# CC_AMP.net
KiCad netlist of a schematic drawn in Altium Designer
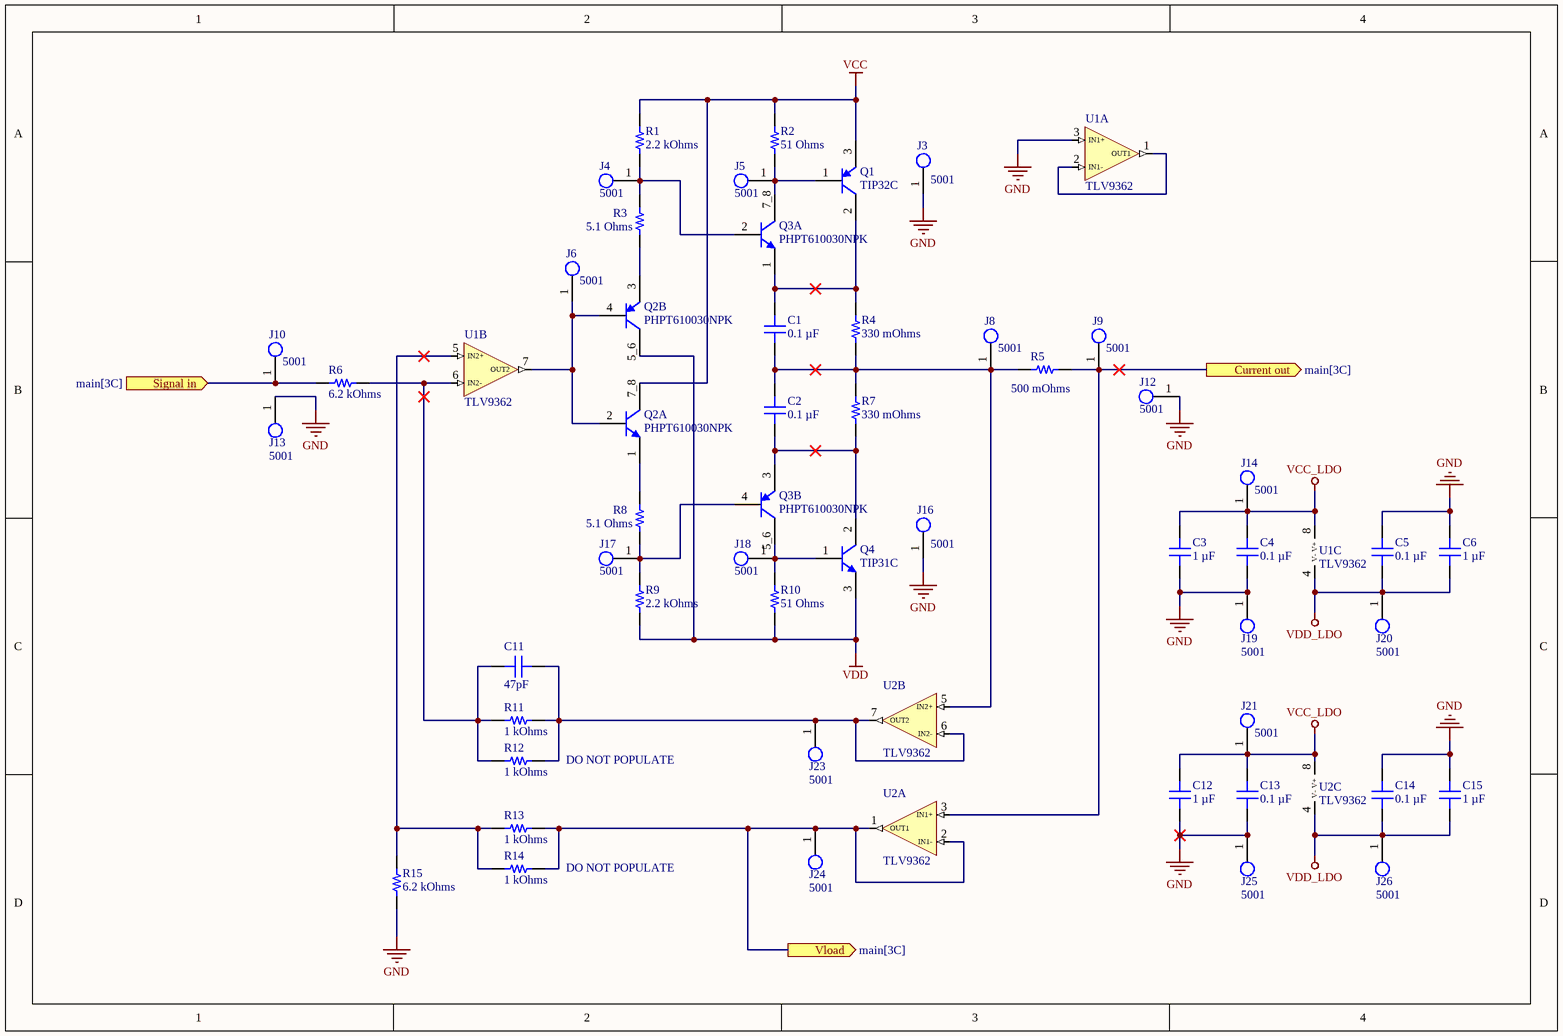
[diagram p0: CC_AMP.SchDoc]

(export (version "E")
  (design (tool "Eeschema 10.0.6"))
  (components
    (comp (ref "C1")
      (value "0.1 µF")
      (footprint "CAP 1206_3216 - 0.8MM")
      (description "CAP CER 0.1UF 50V X7R 1206")
      (fields
        (field (name "PART NUMBER") "885012208087")
        (field (name "CAPACITANCE") "0.1 µF")
        (field (name "MANUFACTURER") "Würth Elektronik")
      )
      (libsource (lib "Celestial Altium Library - altium_library") (part "Capacitor"))
    )
    (comp (ref "C2")
      (value "0.1 µF")
      (footprint "CAP 1206_3216 - 0.8MM")
      (description "CAP CER 0.1UF 50V X7R 1206")
      (fields
        (field (name "PART NUMBER") "885012208087")
        (field (name "CAPACITANCE") "0.1 µF")
        (field (name "MANUFACTURER") "Würth Elektronik")
      )
      (libsource (lib "Celestial Altium Library - altium_library") (part "Capacitor"))
    )
    (comp (ref "C3")
      (value "1 µF")
      (footprint "CAP 1206_3216 - 0.8MM")
      (description "CAP CER 1UF 50V X7R 1206")
      (fields
        (field (name "PART NUMBER") "885012208093")
        (field (name "CAPACITANCE") "1 µF")
        (field (name "MANUFACTURER") "Würth Elektronik")
      )
      (libsource (lib "Celestial Altium Library - altium_library") (part "Capacitor"))
    )
    (comp (ref "C4")
      (value "0.1 µF")
      (footprint "CAP 1206_3216 - 0.8MM")
      (description "CAP CER 0.1UF 50V X7R 1206")
      (fields
        (field (name "PART NUMBER") "885012208087")
        (field (name "CAPACITANCE") "0.1 µF")
        (field (name "MANUFACTURER") "Würth Elektronik")
      )
      (libsource (lib "Celestial Altium Library - altium_library") (part "Capacitor"))
    )
    (comp (ref "C5")
      (value "0.1 µF")
      (footprint "CAP 1206_3216 - 0.8MM")
      (description "CAP CER 0.1UF 50V X7R 1206")
      (fields
        (field (name "PART NUMBER") "885012208087")
        (field (name "CAPACITANCE") "0.1 µF")
        (field (name "MANUFACTURER") "Würth Elektronik")
      )
      (libsource (lib "Celestial Altium Library - altium_library") (part "Capacitor"))
    )
    (comp (ref "C6")
      (value "1 µF")
      (footprint "CAP 1206_3216 - 0.8MM")
      (description "CAP CER 1UF 50V X7R 1206")
      (fields
        (field (name "PART NUMBER") "885012208093")
        (field (name "CAPACITANCE") "1 µF")
        (field (name "MANUFACTURER") "Würth Elektronik")
      )
      (libsource (lib "Celestial Altium Library - altium_library") (part "Capacitor"))
    )
    (comp (ref "C11")
      (value "47pF")
      (footprint "CAP 1206_3216 - 1.8MM")
      (description "CAP CER 47PF 1KV C0G/NP0 1206")
      (fields
        (field (name "PART NUMBER") "1206AA470KAT1A")
        (field (name "CAPACITANCE") "47pF")
        (field (name "MANUFACTURER") "AVX Corporation")
      )
      (libsource (lib "Celestial Altium Library - altium_library") (part "Capacitor"))
    )
    (comp (ref "C12")
      (value "1 µF")
      (footprint "CAP 1206_3216 - 0.8MM")
      (description "CAP CER 1UF 50V X7R 1206")
      (fields
        (field (name "PART NUMBER") "885012208093")
        (field (name "CAPACITANCE") "1 µF")
        (field (name "MANUFACTURER") "Würth Elektronik")
      )
      (libsource (lib "Celestial Altium Library - altium_library") (part "Capacitor"))
    )
    (comp (ref "C13")
      (value "0.1 µF")
      (footprint "CAP 1206_3216 - 0.8MM")
      (description "CAP CER 0.1UF 50V X7R 1206")
      (fields
        (field (name "PART NUMBER") "885012208087")
        (field (name "CAPACITANCE") "0.1 µF")
        (field (name "MANUFACTURER") "Würth Elektronik")
      )
      (libsource (lib "Celestial Altium Library - altium_library") (part "Capacitor"))
    )
    (comp (ref "C14")
      (value "0.1 µF")
      (footprint "CAP 1206_3216 - 0.8MM")
      (description "CAP CER 0.1UF 50V X7R 1206")
      (fields
        (field (name "PART NUMBER") "885012208087")
        (field (name "CAPACITANCE") "0.1 µF")
        (field (name "MANUFACTURER") "Würth Elektronik")
      )
      (libsource (lib "Celestial Altium Library - altium_library") (part "Capacitor"))
    )
    (comp (ref "C15")
      (value "1 µF")
      (footprint "CAP 1206_3216 - 0.8MM")
      (description "CAP CER 1UF 50V X7R 1206")
      (fields
        (field (name "PART NUMBER") "885012208093")
        (field (name "CAPACITANCE") "1 µF")
        (field (name "MANUFACTURER") "Würth Elektronik")
      )
      (libsource (lib "Celestial Altium Library - altium_library") (part "Capacitor"))
    )
    (comp (ref "J3")
      (value "5001")
      (footprint "FP-5001-MFG")
      (description "PC TEST POINT MINIATURE BLACK")
      (libsource (lib "za_koncar") (part "CMP-2000-05181-2"))
    )
    (comp (ref "J4")
      (value "5001")
      (footprint "FP-5001-MFG")
      (description "PC TEST POINT MINIATURE BLACK")
      (libsource (lib "za_koncar") (part "CMP-2000-05181-2"))
    )
    (comp (ref "J5")
      (value "5001")
      (footprint "FP-5001-MFG")
      (description "PC TEST POINT MINIATURE BLACK")
      (libsource (lib "za_koncar") (part "CMP-2000-05181-2"))
    )
    (comp (ref "J6")
      (value "5001")
      (footprint "FP-5001-MFG")
      (description "PC TEST POINT MINIATURE BLACK")
      (libsource (lib "za_koncar") (part "CMP-2000-05181-2"))
    )
    (comp (ref "J8")
      (value "5001")
      (footprint "FP-5001-MFG")
      (description "PC TEST POINT MINIATURE BLACK")
      (libsource (lib "za_koncar") (part "CMP-2000-05181-2"))
    )
    (comp (ref "J9")
      (value "5001")
      (footprint "FP-5001-MFG")
      (description "PC TEST POINT MINIATURE BLACK")
      (libsource (lib "za_koncar") (part "CMP-2000-05181-2"))
    )
    (comp (ref "J10")
      (value "5001")
      (footprint "FP-5001-MFG")
      (description "PC TEST POINT MINIATURE BLACK")
      (libsource (lib "za_koncar") (part "CMP-2000-05181-2"))
    )
    (comp (ref "J12")
      (value "5001")
      (footprint "FP-5001-MFG")
      (description "PC TEST POINT MINIATURE BLACK")
      (libsource (lib "za_koncar") (part "CMP-2000-05181-2"))
    )
    (comp (ref "J13")
      (value "5001")
      (footprint "FP-5001-MFG")
      (description "PC TEST POINT MINIATURE BLACK")
      (libsource (lib "za_koncar") (part "CMP-2000-05181-2"))
    )
    (comp (ref "J14")
      (value "5001")
      (footprint "FP-5001-MFG")
      (description "PC TEST POINT MINIATURE BLACK")
      (libsource (lib "za_koncar") (part "CMP-2000-05181-2"))
    )
    (comp (ref "J16")
      (value "5001")
      (footprint "FP-5001-MFG")
      (description "PC TEST POINT MINIATURE BLACK")
      (libsource (lib "za_koncar") (part "CMP-2000-05181-2"))
    )
    (comp (ref "J17")
      (value "5001")
      (footprint "FP-5001-MFG")
      (description "PC TEST POINT MINIATURE BLACK")
      (libsource (lib "za_koncar") (part "CMP-2000-05181-2"))
    )
    (comp (ref "J18")
      (value "5001")
      (footprint "FP-5001-MFG")
      (description "PC TEST POINT MINIATURE BLACK")
      (libsource (lib "za_koncar") (part "CMP-2000-05181-2"))
    )
    (comp (ref "J19")
      (value "5001")
      (footprint "FP-5001-MFG")
      (description "PC TEST POINT MINIATURE BLACK")
      (libsource (lib "za_koncar") (part "CMP-2000-05181-2"))
    )
    (comp (ref "J20")
      (value "5001")
      (footprint "FP-5001-MFG")
      (description "PC TEST POINT MINIATURE BLACK")
      (libsource (lib "za_koncar") (part "CMP-2000-05181-2"))
    )
    (comp (ref "J21")
      (value "5001")
      (footprint "FP-5001-MFG")
      (description "PC TEST POINT MINIATURE BLACK")
      (libsource (lib "za_koncar") (part "CMP-2000-05181-2"))
    )
    (comp (ref "J23")
      (value "5001")
      (footprint "FP-5001-MFG")
      (description "PC TEST POINT MINIATURE BLACK")
      (libsource (lib "za_koncar") (part "CMP-2000-05181-2"))
    )
    (comp (ref "J24")
      (value "5001")
      (footprint "FP-5001-MFG")
      (description "PC TEST POINT MINIATURE BLACK")
      (libsource (lib "za_koncar") (part "CMP-2000-05181-2"))
    )
    (comp (ref "J25")
      (value "5001")
      (footprint "FP-5001-MFG")
      (description "PC TEST POINT MINIATURE BLACK")
      (libsource (lib "za_koncar") (part "CMP-2000-05181-2"))
    )
    (comp (ref "J26")
      (value "5001")
      (footprint "FP-5001-MFG")
      (description "PC TEST POINT MINIATURE BLACK")
      (libsource (lib "za_koncar") (part "CMP-2000-05181-2"))
    )
    (comp (ref "Q1")
      (value "TIP32C")
      (footprint "ONSC-TO-220-3-221A-09")
      (description "Complementary Silicon Plastic Power Transistor, 3-Pin TO-220, Tube")
      (fields (field (name "MANUFACTURER") "On Semiconductor"))
      (libsource (lib "ON Semi General Purpose Transistors") (part "TIP32C"))
    )
    (comp (ref "Q2")
      (value "PHPT610030NPK")
      (footprint "TRANS_BUK9K18-40E,115")
      (libsource (lib "za_koncar") (part "PHPT610030NPK"))
    )
    (comp (ref "Q3")
      (value "PHPT610030NPK")
      (footprint "TRANS_BUK9K18-40E,115")
      (libsource (lib "za_koncar") (part "PHPT610030NPK"))
    )
    (comp (ref "Q4")
      (value "TIP31C")
      (footprint "ONSC-TO-220-3-221A-09")
      (description "Complementary Silicon Plastic Power Transistor, 3-Pin TO-220, Tube")
      (fields (field (name "MANUFACTURER") "On Semiconductor"))
      (libsource (lib "ON Semi General Purpose Transistors") (part "TIP31C"))
    )
    (comp (ref "R1")
      (value "2.2 kOhms")
      (footprint "RES 1206_3216")
      (description "RES SMD 2.2K OHM 5% 1/4W 1206")
      (fields
        (field (name "PART NUMBER") "ERJ-8GEYJ222V")
        (field (name "MANUFACTURER") "Panasonic Electronic Components")
      )
      (libsource (lib "Celestial Altium Library - altium_library") (part "Resistor"))
    )
    (comp (ref "R2")
      (value "51 Ohms")
      (footprint "RES 1206_3216")
      (description "RES SMD 51 OHM 5% 1/4W 1206")
      (fields
        (field (name "PART NUMBER") "ERJ-8GEYJ510V")
        (field (name "MANUFACTURER") "Panasonic Electronic Components")
      )
      (libsource (lib "Celestial Altium Library - altium_library") (part "Resistor"))
    )
    (comp (ref "R3")
      (value "5.1 Ohms")
      (footprint "RES 1206_3216")
      (description "RES SMD 5.1 OHM 5% 1/4W 1206")
      (fields
        (field (name "PART NUMBER") "ERJ-8GEYJ5R1V")
        (field (name "MANUFACTURER") "Panasonic Electronic Components")
      )
      (libsource (lib "Celestial Altium Library - altium_library") (part "Resistor"))
    )
    (comp (ref "R4")
      (value "330 mOhms")
      (footprint "STACKPOLE CSR2512")
      (description "RES 0.33 OHM 1% 2W 2512")
      (fields
        (field (name "PART NUMBER") "CSRN2512FKR330")
        (field (name "MANUFACTURER") "Stackpole Electronics Inc")
      )
      (libsource (lib "Celestial Altium Library - altium_library") (part "Resistor"))
    )
    (comp (ref "R5")
      (value "500 mOhms")
      (footprint "STACKPOLE CSR2512")
      (description "RES 0.5 OHM 1% 2W 2512")
      (fields
        (field (name "PART NUMBER") "CSRN2512FKR500")
        (field (name "MANUFACTURER") "Stackpole Electronics Inc")
      )
      (libsource (lib "Celestial Altium Library - altium_library") (part "Resistor"))
    )
    (comp (ref "R6")
      (value "6.2 kOhms")
      (footprint "RES 1206_3216")
      (description "RES SMD 6.2K OHM 0.1% 1/4W 1206")
      (fields
        (field (name "PART NUMBER") "ERA-8AEB622V")
        (field (name "MANUFACTURER") "Panasonic Electronic Components")
      )
      (libsource (lib "Celestial Altium Library - altium_library") (part "Resistor"))
    )
    (comp (ref "R7")
      (value "330 mOhms")
      (footprint "STACKPOLE CSR2512")
      (description "RES 0.33 OHM 1% 2W 2512")
      (fields
        (field (name "PART NUMBER") "CSRN2512FKR330")
        (field (name "MANUFACTURER") "Stackpole Electronics Inc")
      )
      (libsource (lib "Celestial Altium Library - altium_library") (part "Resistor"))
    )
    (comp (ref "R8")
      (value "5.1 Ohms")
      (footprint "RES 1206_3216")
      (description "RES SMD 5.1 OHM 5% 1/4W 1206")
      (fields
        (field (name "PART NUMBER") "ERJ-8GEYJ5R1V")
        (field (name "MANUFACTURER") "Panasonic Electronic Components")
      )
      (libsource (lib "Celestial Altium Library - altium_library") (part "Resistor"))
    )
    (comp (ref "R9")
      (value "2.2 kOhms")
      (footprint "RES 1206_3216")
      (description "RES SMD 2.2K OHM 5% 1/4W 1206")
      (fields
        (field (name "PART NUMBER") "ERJ-8GEYJ222V")
        (field (name "MANUFACTURER") "Panasonic Electronic Components")
      )
      (libsource (lib "Celestial Altium Library - altium_library") (part "Resistor"))
    )
    (comp (ref "R10")
      (value "51 Ohms")
      (footprint "RES 1206_3216")
      (description "RES SMD 51 OHM 5% 1/4W 1206")
      (fields
        (field (name "PART NUMBER") "ERJ-8GEYJ510V")
        (field (name "MANUFACTURER") "Panasonic Electronic Components")
      )
      (libsource (lib "Celestial Altium Library - altium_library") (part "Resistor"))
    )
    (comp (ref "R11")
      (value "1 kOhms")
      (footprint "RES 1206_3216")
      (description "RES SMD 1K OHM 0.1% 1/4W 1206")
      (fields
        (field (name "PART NUMBER") "ERA-8AEB102V")
        (field (name "MANUFACTURER") "Panasonic Electronic Components")
      )
      (libsource (lib "Celestial Altium Library - altium_library") (part "Resistor"))
    )
    (comp (ref "R12")
      (value "1 kOhms")
      (footprint "RES 1206_3216")
      (description "RES SMD 1K OHM 0.1% 1/4W 1206")
      (fields
        (field (name "PART NUMBER") "ERA-8AEB102V")
        (field (name "MANUFACTURER") "Panasonic Electronic Components")
      )
      (libsource (lib "Celestial Altium Library - altium_library") (part "Resistor"))
    )
    (comp (ref "R13")
      (value "1 kOhms")
      (footprint "RES 1206_3216")
      (description "RES SMD 1K OHM 0.1% 1/4W 1206")
      (fields
        (field (name "PART NUMBER") "ERA-8AEB102V")
        (field (name "MANUFACTURER") "Panasonic Electronic Components")
      )
      (libsource (lib "Celestial Altium Library - altium_library") (part "Resistor"))
    )
    (comp (ref "R14")
      (value "1 kOhms")
      (footprint "RES 1206_3216")
      (description "RES SMD 1K OHM 0.1% 1/4W 1206")
      (fields
        (field (name "PART NUMBER") "ERA-8AEB102V")
        (field (name "MANUFACTURER") "Panasonic Electronic Components")
      )
      (libsource (lib "Celestial Altium Library - altium_library") (part "Resistor"))
    )
    (comp (ref "R15")
      (value "6.2 kOhms")
      (footprint "RES 1206_3216")
      (description "RES SMD 6.2K OHM 0.1% 1/4W 1206")
      (fields
        (field (name "PART NUMBER") "ERA-8AEB622V")
        (field (name "MANUFACTURER") "Panasonic Electronic Components")
      )
      (libsource (lib "Celestial Altium Library - altium_library") (part "Resistor"))
    )
    (comp (ref "U1")
      (value "TLV9362")
      (footprint "za_koncar:SOIC8-127P600X175-8N")
      (description "TLV936x 10-MHz, 40-V, RRO, Operational Amplifie")
      (libsource (lib "za_koncar") (part "TLV9362"))
    )
    (comp (ref "U2")
      (value "TLV9362")
      (footprint "za_koncar:SOIC8-127P600X175-8N")
      (description "TLV936x 10-MHz, 40-V, RRO, Operational Amplifie")
      (libsource (lib "za_koncar") (part "TLV9362"))
    )
  )
  (nets
    (net (code "1") (name "/Current out") (class "Default")
      (node (ref "J9") (pin "1") (pinfunction "1_1") (pintype "passive"))
      (node (ref "R5") (pin "1") (pinfunction "1_1") (pintype "passive"))
      (node (ref "U2") (pin "3") (pinfunction "IN1+_3") (pintype "input"))
    )
    (net (code "2") (name "/Signal in") (class "Default")
      (node (ref "J10") (pin "1") (pinfunction "1_1") (pintype "passive"))
      (node (ref "R6") (pin "2") (pinfunction "2_2") (pintype "passive"))
    )
    (net (code "3") (name "/Vload") (class "Default")
      (node (ref "J24") (pin "1") (pinfunction "1_1") (pintype "passive"))
      (node (ref "R13") (pin "2") (pinfunction "2_2") (pintype "passive"))
      (node (ref "R14") (pin "2") (pinfunction "2_2") (pintype "passive"))
      (node (ref "U2") (pin "1") (pinfunction "OUT1_1") (pintype "output"))
      (node (ref "U2") (pin "2") (pinfunction "IN1-_2") (pintype "input"))
    )
    (net (code "4") (name "GND") (class "Default")
      (node (ref "C12") (pin "1") (pinfunction "1_1") (pintype "passive"))
      (node (ref "C13") (pin "1") (pinfunction "1_1") (pintype "passive"))
      (node (ref "C14") (pin "2") (pinfunction "2_2") (pintype "passive"))
      (node (ref "C15") (pin "2") (pinfunction "2_2") (pintype "passive"))
      (node (ref "C3") (pin "1") (pinfunction "1_1") (pintype "passive"))
      (node (ref "C4") (pin "1") (pinfunction "1_1") (pintype "passive"))
      (node (ref "C5") (pin "2") (pinfunction "2_2") (pintype "passive"))
      (node (ref "C6") (pin "2") (pinfunction "2_2") (pintype "passive"))
      (node (ref "J12") (pin "1") (pinfunction "1_1") (pintype "passive"))
      (node (ref "J13") (pin "1") (pinfunction "1_1") (pintype "passive"))
      (node (ref "J16") (pin "1") (pinfunction "1_1") (pintype "passive"))
      (node (ref "J19") (pin "1") (pinfunction "1_1") (pintype "passive"))
      (node (ref "J25") (pin "1") (pinfunction "1_1") (pintype "passive"))
      (node (ref "J3") (pin "1") (pinfunction "1_1") (pintype "passive"))
      (node (ref "R15") (pin "1") (pinfunction "1_1") (pintype "passive"))
      (node (ref "U1") (pin "3") (pinfunction "IN1+_3") (pintype "input"))
    )
    (net (code "5") (name "Net-(Q1-B)") (class "Default")
      (node (ref "J5") (pin "1") (pinfunction "1_1") (pintype "passive"))
      (node (ref "Q1") (pin "1") (pinfunction "B_1") (pintype "passive"))
      (node (ref "Q3") (pin "7_8") (pinfunction "C1_7_8") (pintype "passive"))
      (node (ref "R2") (pin "1") (pinfunction "1_1") (pintype "passive"))
    )
    (net (code "6") (name "Net-(Q1-C)") (class "Default")
      (node (ref "C1") (pin "2") (pinfunction "2_2") (pintype "passive"))
      (node (ref "Q1") (pin "2") (pinfunction "C_2") (pintype "passive"))
      (node (ref "Q3") (pin "1") (pinfunction "E1_1") (pintype "passive"))
      (node (ref "R4") (pin "2") (pinfunction "2_2") (pintype "passive"))
    )
    (net (code "7") (name "Net-(Q2A-B1)") (class "Default")
      (node (ref "J6") (pin "1") (pinfunction "1_1") (pintype "passive"))
      (node (ref "Q2") (pin "2") (pinfunction "B1_2") (pintype "passive"))
      (node (ref "Q2") (pin "4") (pinfunction "B2_4") (pintype "passive"))
      (node (ref "U1") (pin "7") (pinfunction "OUT2_7") (pintype "output"))
    )
    (net (code "8") (name "Net-(Q2A-E1)") (class "Default")
      (node (ref "Q2") (pin "1") (pinfunction "E1_1") (pintype "passive"))
      (node (ref "R8") (pin "2") (pinfunction "2_2") (pintype "passive"))
    )
    (net (code "9") (name "Net-(Q2B-E2)") (class "Default")
      (node (ref "Q2") (pin "3") (pinfunction "E2_3") (pintype "passive"))
      (node (ref "R3") (pin "1") (pinfunction "1_1") (pintype "passive"))
    )
    (net (code "10") (name "Net-(Q3A-B1)") (class "Default")
      (node (ref "J4") (pin "1") (pinfunction "1_1") (pintype "passive"))
      (node (ref "Q3") (pin "2") (pinfunction "B1_2") (pintype "passive"))
      (node (ref "R1") (pin "1") (pinfunction "1_1") (pintype "passive"))
      (node (ref "R3") (pin "2") (pinfunction "2_2") (pintype "passive"))
    )
    (net (code "11") (name "Net-(Q3B-B2)") (class "Default")
      (node (ref "J17") (pin "1") (pinfunction "1_1") (pintype "passive"))
      (node (ref "Q3") (pin "4") (pinfunction "B2_4") (pintype "passive"))
      (node (ref "R8") (pin "1") (pinfunction "1_1") (pintype "passive"))
      (node (ref "R9") (pin "2") (pinfunction "2_2") (pintype "passive"))
    )
    (net (code "12") (name "Net-(Q3B-C2)") (class "Default")
      (node (ref "J18") (pin "1") (pinfunction "1_1") (pintype "passive"))
      (node (ref "Q3") (pin "5_6") (pinfunction "C2_5_6") (pintype "passive"))
      (node (ref "Q4") (pin "1") (pinfunction "B_1") (pintype "passive"))
      (node (ref "R10") (pin "2") (pinfunction "2_2") (pintype "passive"))
    )
    (net (code "13") (name "Net-(Q3B-E2)") (class "Default")
      (node (ref "C2") (pin "1") (pinfunction "1_1") (pintype "passive"))
      (node (ref "Q3") (pin "3") (pinfunction "E2_3") (pintype "passive"))
      (node (ref "Q4") (pin "2") (pinfunction "C_2") (pintype "passive"))
      (node (ref "R7") (pin "1") (pinfunction "1_1") (pintype "passive"))
    )
    (net (code "14") (name "Net-(U1A-IN1-)") (class "Default")
      (node (ref "U1") (pin "1") (pinfunction "OUT1_1") (pintype "output"))
      (node (ref "U1") (pin "2") (pinfunction "IN1-_2") (pintype "input"))
    )
    (net (code "15") (name "Net-(U1B-IN2+)") (class "Default")
      (node (ref "R13") (pin "1") (pinfunction "1_1") (pintype "passive"))
      (node (ref "R14") (pin "1") (pinfunction "1_1") (pintype "passive"))
      (node (ref "R15") (pin "2") (pinfunction "2_2") (pintype "passive"))
      (node (ref "U1") (pin "5") (pinfunction "IN2+_5") (pintype "input"))
    )
    (net (code "16") (name "Net-(U1B-IN2-)") (class "Default")
      (node (ref "C11") (pin "1") (pinfunction "1_1") (pintype "passive"))
      (node (ref "R11") (pin "1") (pinfunction "1_1") (pintype "passive"))
      (node (ref "R12") (pin "1") (pinfunction "1_1") (pintype "passive"))
      (node (ref "R6") (pin "1") (pinfunction "1_1") (pintype "passive"))
      (node (ref "U1") (pin "6") (pinfunction "IN2-_6") (pintype "input"))
    )
    (net (code "17") (name "Net-(U2B-IN2+)") (class "Default")
      (node (ref "C1") (pin "1") (pinfunction "1_1") (pintype "passive"))
      (node (ref "C2") (pin "2") (pinfunction "2_2") (pintype "passive"))
      (node (ref "J8") (pin "1") (pinfunction "1_1") (pintype "passive"))
      (node (ref "R4") (pin "1") (pinfunction "1_1") (pintype "passive"))
      (node (ref "R5") (pin "2") (pinfunction "2_2") (pintype "passive"))
      (node (ref "R7") (pin "2") (pinfunction "2_2") (pintype "passive"))
      (node (ref "U2") (pin "5") (pinfunction "IN2+_5") (pintype "input"))
    )
    (net (code "18") (name "Net-(U2B-IN2-)") (class "Default")
      (node (ref "C11") (pin "2") (pinfunction "2_2") (pintype "passive"))
      (node (ref "J23") (pin "1") (pinfunction "1_1") (pintype "passive"))
      (node (ref "R11") (pin "2") (pinfunction "2_2") (pintype "passive"))
      (node (ref "R12") (pin "2") (pinfunction "2_2") (pintype "passive"))
      (node (ref "U2") (pin "6") (pinfunction "IN2-_6") (pintype "input"))
      (node (ref "U2") (pin "7") (pinfunction "OUT2_7") (pintype "output"))
    )
    (net (code "19") (name "VCC") (class "Default")
      (node (ref "Q1") (pin "3") (pinfunction "E_3") (pintype "passive"))
      (node (ref "Q2") (pin "7_8") (pinfunction "C1_7_8") (pintype "passive"))
      (node (ref "R1") (pin "2") (pinfunction "2_2") (pintype "passive"))
      (node (ref "R2") (pin "2") (pinfunction "2_2") (pintype "passive"))
    )
    (net (code "20") (name "VCC_LDO") (class "Default")
      (node (ref "C12") (pin "2") (pinfunction "2_2") (pintype "passive"))
      (node (ref "C13") (pin "2") (pinfunction "2_2") (pintype "passive"))
      (node (ref "C3") (pin "2") (pinfunction "2_2") (pintype "passive"))
      (node (ref "C4") (pin "2") (pinfunction "2_2") (pintype "passive"))
      (node (ref "J14") (pin "1") (pinfunction "1_1") (pintype "passive"))
      (node (ref "J21") (pin "1") (pinfunction "1_1") (pintype "passive"))
      (node (ref "U1") (pin "8") (pinfunction "V+_8") (pintype "power_in"))
      (node (ref "U2") (pin "8") (pinfunction "V+_8") (pintype "power_in"))
    )
    (net (code "21") (name "VDD") (class "Default")
      (node (ref "Q2") (pin "5_6") (pinfunction "C2_5_6") (pintype "passive"))
      (node (ref "Q4") (pin "3") (pinfunction "E_3") (pintype "passive"))
      (node (ref "R10") (pin "1") (pinfunction "1_1") (pintype "passive"))
      (node (ref "R9") (pin "1") (pinfunction "1_1") (pintype "passive"))
    )
    (net (code "22") (name "VDD_LDO") (class "Default")
      (node (ref "C14") (pin "1") (pinfunction "1_1") (pintype "passive"))
      (node (ref "C15") (pin "1") (pinfunction "1_1") (pintype "passive"))
      (node (ref "C5") (pin "1") (pinfunction "1_1") (pintype "passive"))
      (node (ref "C6") (pin "1") (pinfunction "1_1") (pintype "passive"))
      (node (ref "J20") (pin "1") (pinfunction "1_1") (pintype "passive"))
      (node (ref "J26") (pin "1") (pinfunction "1_1") (pintype "passive"))
      (node (ref "U1") (pin "4") (pinfunction "V-_4") (pintype "power_in"))
      (node (ref "U2") (pin "4") (pinfunction "V-_4") (pintype "power_in"))
    )
  )
)
